# LCT_M3_SCH.net
KiCad netlist of a schematic drawn in Altium Designer
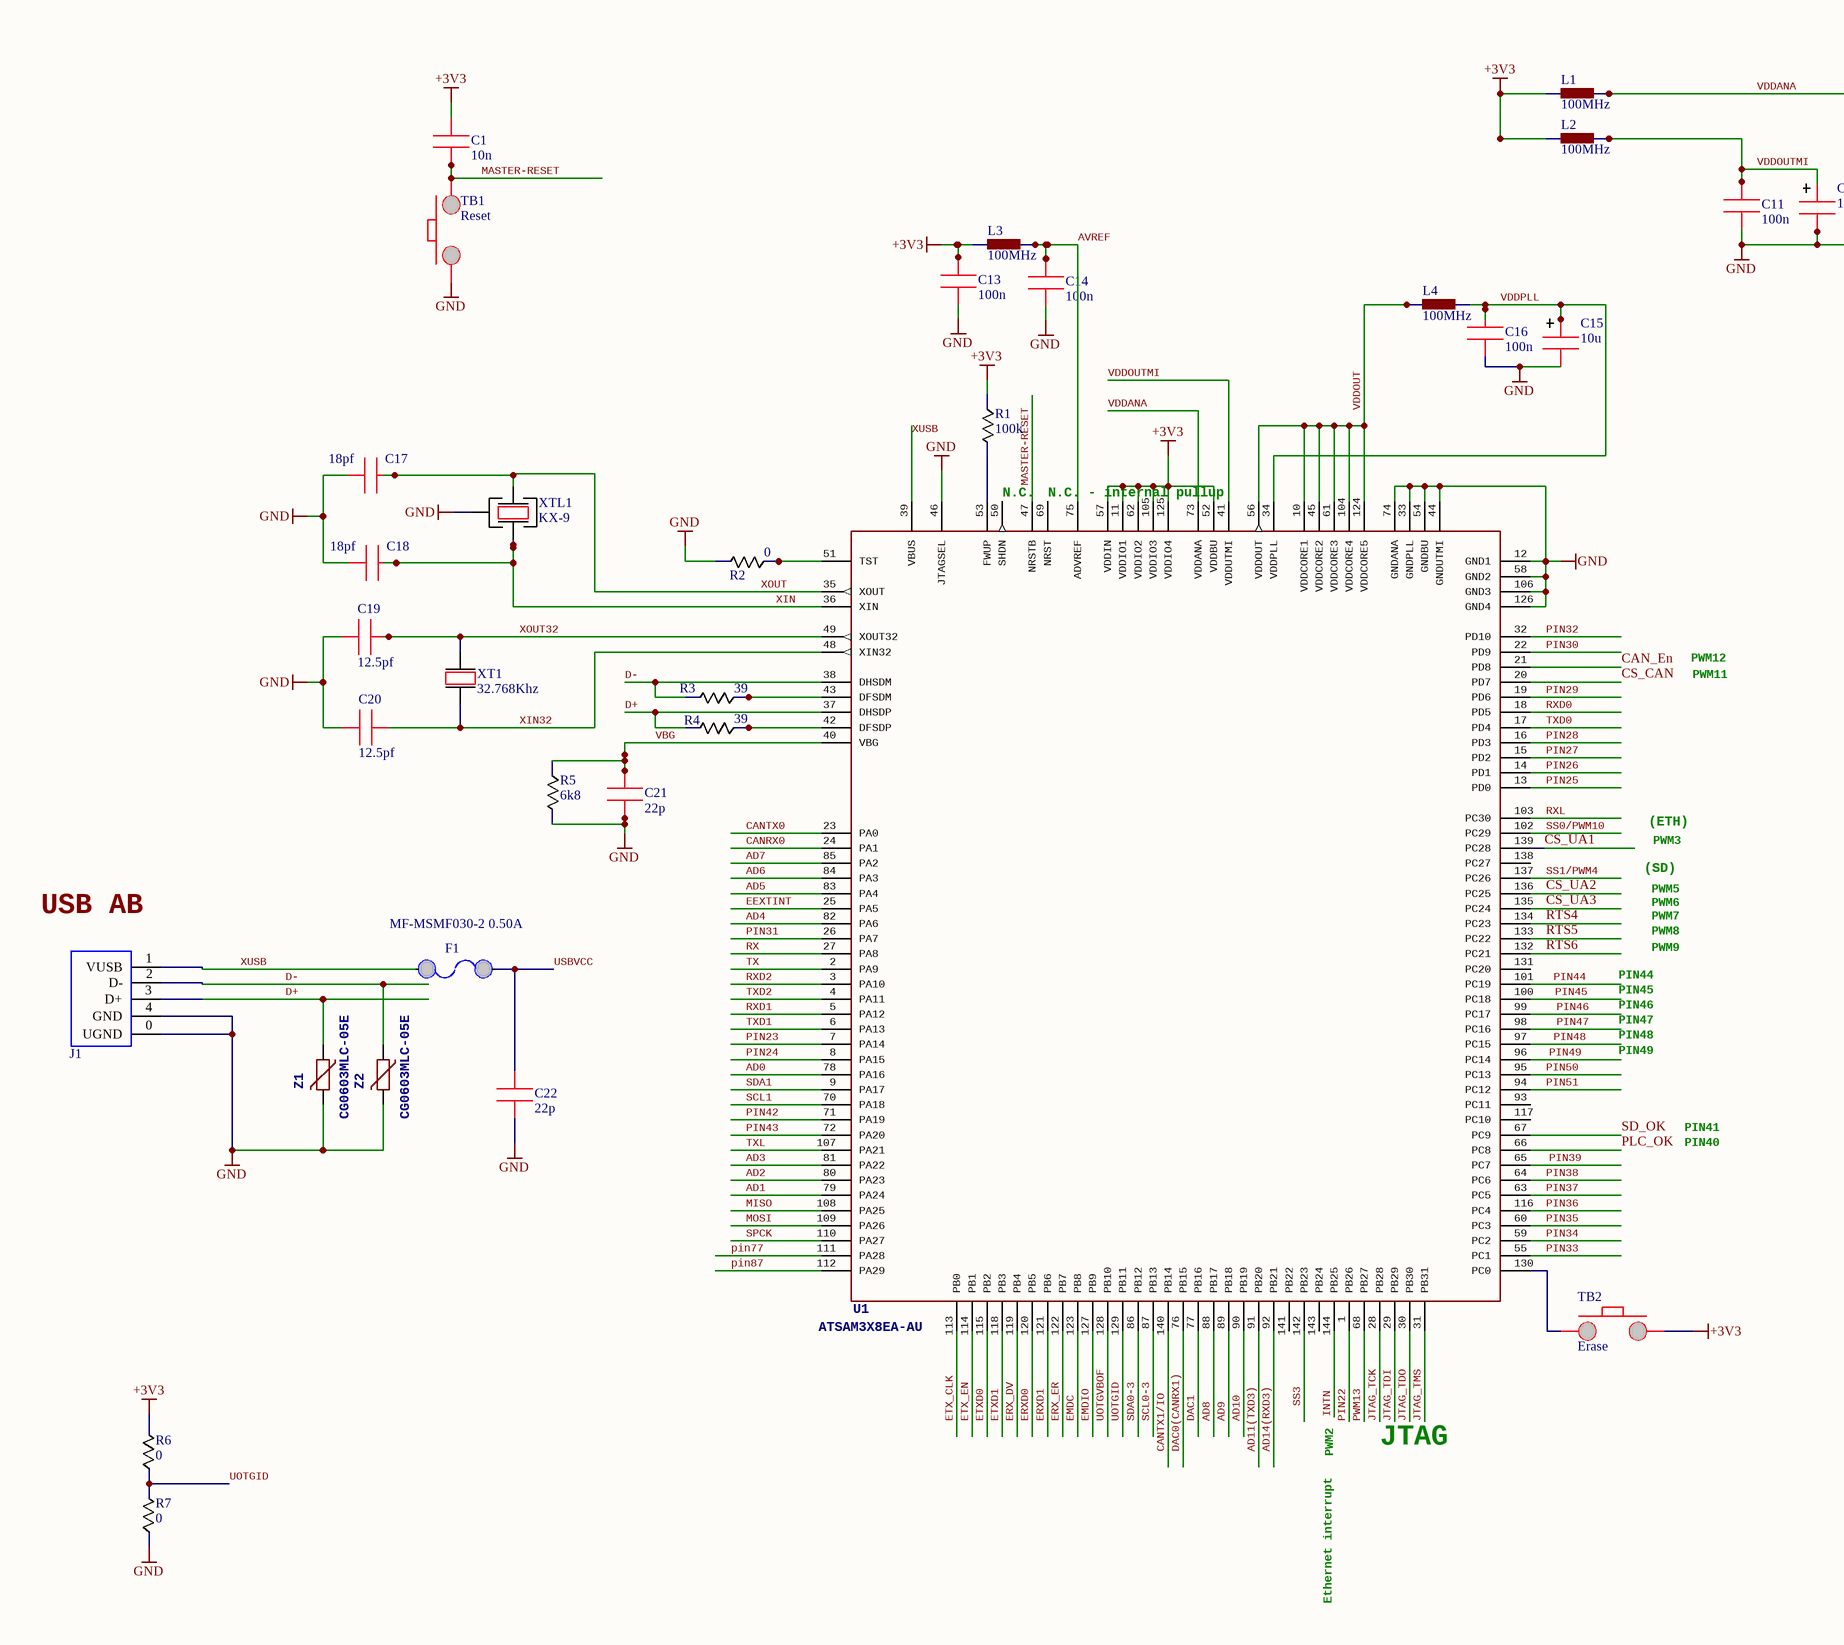
[diagram p0: LCT M3 SCH.SchDoc, left]
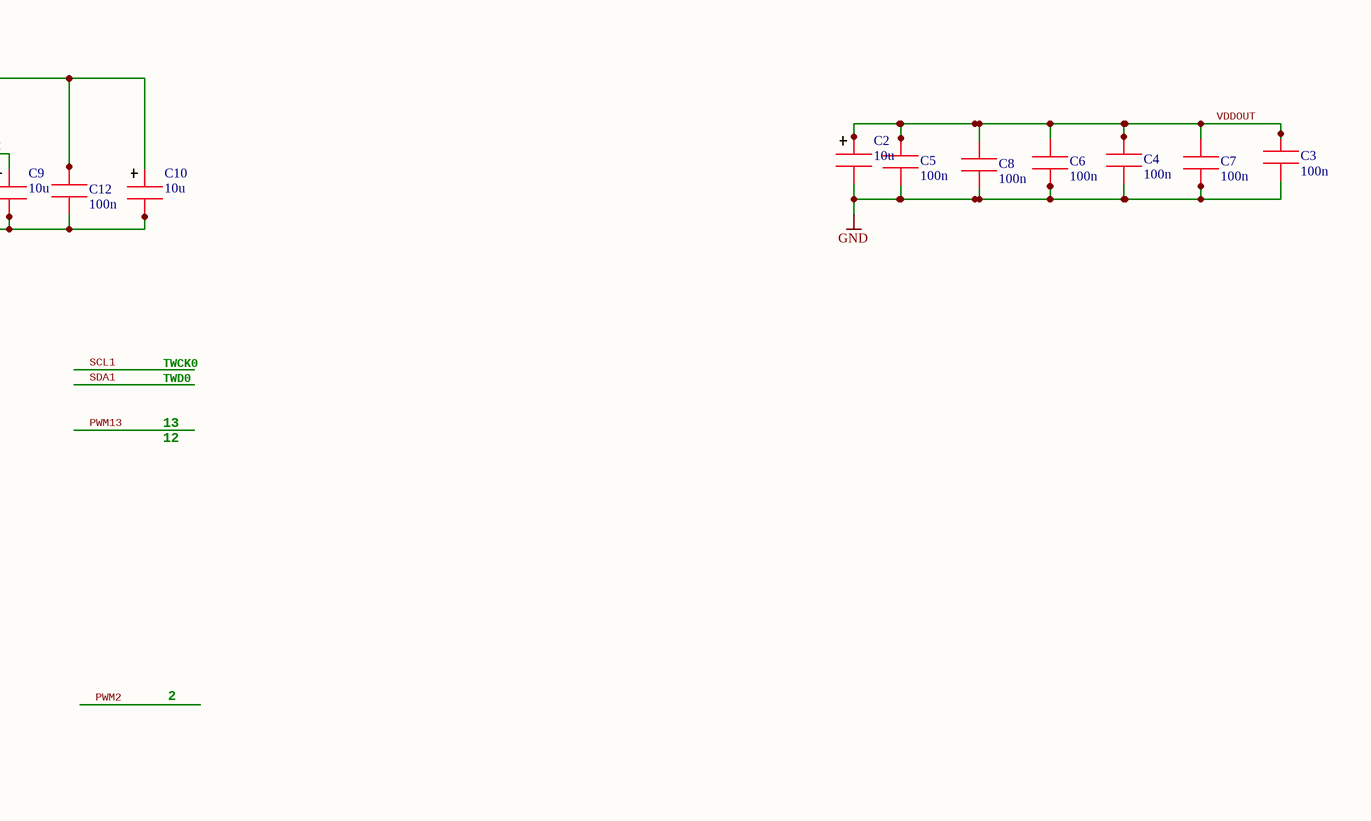
[diagram p1: LCT M3 SCH.SchDoc, right]

(export (version "E")
  (design (tool "Eeschema 10.0.6"))
  (components
    (comp (ref "C1") (value "10n") (footprint "0603") (libsource (lib "kontr") (part "Capasitor 0805")))
    (comp (ref "C2")
      (value "10u")
      (footprint "1206")
      (description "TAJA156K010RNJ")
      (libsource (lib "kontr") (part "1206 Cap El"))
    )
    (comp (ref "C3") (value "100n") (footprint "0603") (libsource (lib "kontr") (part "Capasitor 0805")))
    (comp (ref "C4") (value "100n") (footprint "0603") (libsource (lib "kontr") (part "Capasitor 0805")))
    (comp (ref "C5") (value "100n") (footprint "0603") (libsource (lib "kontr") (part "Capasitor 0805")))
    (comp (ref "C6") (value "100n") (footprint "0603") (libsource (lib "kontr") (part "Capasitor 0805")))
    (comp (ref "C7") (value "100n") (footprint "0603") (libsource (lib "kontr") (part "Capasitor 0805")))
    (comp (ref "C8") (value "100n") (footprint "0603") (libsource (lib "kontr") (part "Capasitor 0805")))
    (comp (ref "C9")
      (value "10u")
      (footprint "1206")
      (description "TAJA156K010RNJ")
      (libsource (lib "kontr") (part "1206 Cap El"))
    )
    (comp (ref "C10")
      (value "10u")
      (footprint "1206")
      (description "TAJA156K010RNJ")
      (libsource (lib "kontr") (part "1206 Cap El"))
    )
    (comp (ref "C11") (value "100n") (footprint "0603") (libsource (lib "kontr") (part "Capasitor 0805")))
    (comp (ref "C12") (value "100n") (footprint "0603") (libsource (lib "kontr") (part "Capasitor 0805")))
    (comp (ref "C13") (value "100n") (footprint "0603") (libsource (lib "kontr") (part "Capasitor 0805")))
    (comp (ref "C14") (value "100n") (footprint "0603") (libsource (lib "kontr") (part "Capasitor 0805")))
    (comp (ref "C15")
      (value "10u")
      (footprint "1206")
      (description "TAJA156K010RNJ")
      (libsource (lib "kontr") (part "1206 Cap El"))
    )
    (comp (ref "C16") (value "100n") (footprint "0603") (libsource (lib "kontr") (part "Capasitor 0805")))
    (comp (ref "C17") (value "18pf") (footprint "0603") (libsource (lib "kontr") (part "Capasitor 0805")))
    (comp (ref "C18") (value "18pf") (footprint "0603") (libsource (lib "kontr") (part "Capasitor 0805")))
    (comp (ref "C19") (value "12.5pf") (footprint "0603") (libsource (lib "kontr") (part "Capasitor 0805")))
    (comp (ref "C20") (value "12.5pf") (footprint "0603") (libsource (lib "kontr") (part "Capasitor 0805")))
    (comp (ref "C21") (value "22p") (footprint "0603") (libsource (lib "kontr") (part "Capasitor 0805")))
    (comp (ref "C22") (value "22p") (footprint "0603") (libsource (lib "kontr") (part "Capasitor 0805")))
    (comp (ref "F1")
      (value "MF-MSMF030-2 0.50A")
      (footprint "Fuse PTS")
      (libsource (lib "kontr") (part "Fuse PTS"))
    )
    (comp (ref "J1") (value "USBB-1J") (footprint "USB B") (libsource (lib "kontr") (part "USBB-1J")))
    (comp (ref "L1") (value "100MHz") (footprint "0805") (libsource (lib "kontr") (part "BLM21PG220SN1D")))
    (comp (ref "L2") (value "100MHz") (footprint "0805") (libsource (lib "kontr") (part "BLM21PG220SN1D")))
    (comp (ref "L3") (value "100MHz") (footprint "0805") (libsource (lib "kontr") (part "BLM21PG220SN1D")))
    (comp (ref "L4") (value "100MHz") (footprint "0805") (libsource (lib "kontr") (part "BLM21PG220SN1D")))
    (comp (ref "R1")
      (value "100k")
      (footprint "0603")
      (description "0805 SMD Resistor")
      (libsource (lib "kontr") (part "Resistor 0805"))
    )
    (comp (ref "R2")
      (value "0")
      (footprint "0603")
      (description "0805 SMD Resistor")
      (libsource (lib "kontr") (part "Resistor 0805"))
    )
    (comp (ref "R3")
      (value "39")
      (footprint "0603")
      (description "0805 SMD Resistor")
      (libsource (lib "kontr") (part "Resistor 0805"))
    )
    (comp (ref "R4")
      (value "39")
      (footprint "0603")
      (description "0805 SMD Resistor")
      (libsource (lib "kontr") (part "Resistor 0805"))
    )
    (comp (ref "R5")
      (value "6k8")
      (footprint "0603")
      (description "0805 SMD Resistor")
      (libsource (lib "kontr") (part "Resistor 0805"))
    )
    (comp (ref "R6")
      (value "0")
      (footprint "0603")
      (description "RC0603FR-078K2")
      (libsource (lib "kontr") (part "Resistor 0805"))
    )
    (comp (ref "R7")
      (value "0")
      (footprint "0603")
      (description "RC0603FR-078K2")
      (libsource (lib "kontr") (part "Resistor 0805"))
    )
    (comp (ref "TB1")
      (value "Reset")
      (footprint "IT-1184-160G-g")
      (description "IT-1184-160G-G")
      (libsource (lib "kontr") (part "IT-1184-160G-G"))
    )
    (comp (ref "TB2")
      (value "Erase")
      (footprint "IT-1184-160G-g")
      (description "IT-1184-160G-G")
      (libsource (lib "kontr") (part "IT-1184-160G-G"))
    )
    (comp (ref "U1")
      (value "ATSAM3X8EA-AU")
      (footprint "LQFP144")
      (libsource (lib "SmartPrj") (part "ATSAM3X/AAU"))
    )
    (comp (ref "XT1")
      (value "32.768Khz")
      (footprint "KX – 327")
      (description "KX – 327XS")
      (libsource (lib "kontr") (part "KX – 327XS"))
    )
    (comp (ref "XTL1") (value "KX-9") (footprint "KX-9") (libsource (lib "kontr") (part "KX-9")))
    (comp (ref "Z1")
      (value "CG0603MLC-05E")
      (footprint "0603")
      (description "<b>VARISTOR</b>")
      (libsource (lib "varistor") (part "VARISTORCN0603"))
    )
    (comp (ref "Z2")
      (value "CG0603MLC-05E")
      (footprint "0603")
      (description "<b>VARISTOR</b>")
      (libsource (lib "varistor") (part "VARISTORCN0603"))
    )
  )
  (nets
    (net (code "1") (name "+3V3") (class "Default")
      (node (ref "C1") (pin "2") (pinfunction "2_2") (pintype "passive"))
      (node (ref "C13") (pin "2") (pinfunction "2_2") (pintype "passive"))
      (node (ref "L1") (pin "1") (pintype "passive"))
      (node (ref "L2") (pin "1") (pintype "passive"))
      (node (ref "L3") (pin "1") (pintype "passive"))
      (node (ref "R1") (pin "1") (pintype "passive"))
      (node (ref "R6") (pin "2") (pintype "passive"))
      (node (ref "TB2") (pin "1") (pinfunction "1_1") (pintype "passive"))
      (node (ref "U1") (pin "105") (pinfunction "VDDIO3_105") (pintype "power_in"))
      (node (ref "U1") (pin "11") (pinfunction "VDDIO1_11") (pintype "power_in"))
      (node (ref "U1") (pin "125") (pinfunction "VDDIO4_125") (pintype "power_in"))
      (node (ref "U1") (pin "52") (pinfunction "VDDBU_52") (pintype "power_in"))
      (node (ref "U1") (pin "57") (pinfunction "VDDIN_57") (pintype "power_in"))
      (node (ref "U1") (pin "62") (pinfunction "VDDIO2_62") (pintype "power_in"))
    )
    (net (code "2") (name "/AD0") (class "Default")
      (node (ref "U1") (pin "78") (pinfunction "PA16_78") (pintype "passive"))
    )
    (net (code "3") (name "/AD1") (class "Default")
      (node (ref "U1") (pin "79") (pinfunction "PA24_79") (pintype "passive"))
    )
    (net (code "4") (name "/AD2") (class "Default")
      (node (ref "U1") (pin "80") (pinfunction "PA23_80") (pintype "passive"))
    )
    (net (code "5") (name "/AD3") (class "Default")
      (node (ref "U1") (pin "81") (pinfunction "PA22_81") (pintype "passive"))
    )
    (net (code "6") (name "/AD4") (class "Default")
      (node (ref "U1") (pin "82") (pinfunction "PA6_82") (pintype "passive"))
    )
    (net (code "7") (name "/AD5") (class "Default")
      (node (ref "U1") (pin "83") (pinfunction "PA4_83") (pintype "passive"))
    )
    (net (code "8") (name "/AD6") (class "Default")
      (node (ref "U1") (pin "84") (pinfunction "PA3_84") (pintype "passive"))
    )
    (net (code "9") (name "/AD7") (class "Default")
      (node (ref "U1") (pin "85") (pinfunction "PA2_85") (pintype "passive"))
    )
    (net (code "10") (name "/AD8") (class "Default")
      (node (ref "U1") (pin "88") (pinfunction "PB17_88") (pintype "passive"))
    )
    (net (code "11") (name "/AD9") (class "Default")
      (node (ref "U1") (pin "89") (pinfunction "PB18_89") (pintype "passive"))
    )
    (net (code "12") (name "/AD10") (class "Default")
      (node (ref "U1") (pin "90") (pinfunction "PB19_90") (pintype "passive"))
    )
    (net (code "13") (name "/AD11(TXD3)") (class "Default")
      (node (ref "U1") (pin "91") (pinfunction "PB20_91") (pintype "passive"))
    )
    (net (code "14") (name "/AD14(RXD3)") (class "Default")
      (node (ref "U1") (pin "92") (pinfunction "PB21_92") (pintype "passive"))
    )
    (net (code "15") (name "/AVREF") (class "Default")
      (node (ref "C14") (pin "2") (pinfunction "2_2") (pintype "passive"))
      (node (ref "L3") (pin "2") (pintype "passive"))
      (node (ref "U1") (pin "75") (pinfunction "ADVREF_75") (pintype "power_in"))
    )
    (net (code "16") (name "/CANRX0") (class "Default")
      (node (ref "U1") (pin "24") (pinfunction "PA1_24") (pintype "passive"))
    )
    (net (code "17") (name "/CANTX0") (class "Default")
      (node (ref "U1") (pin "23") (pinfunction "PA0_23") (pintype "passive"))
    )
    (net (code "18") (name "/CANTX1{slash}IO") (class "Default")
      (node (ref "U1") (pin "140") (pinfunction "PB14_140") (pintype "passive"))
    )
    (net (code "19") (name "/CAN_En") (class "Default")
      (node (ref "U1") (pin "21") (pinfunction "PD8_21") (pintype "passive"))
    )
    (net (code "20") (name "/CS_CAN") (class "Default")
      (node (ref "U1") (pin "20") (pinfunction "PD7_20") (pintype "passive"))
    )
    (net (code "21") (name "/CS_UA1") (class "Default")
      (node (ref "U1") (pin "139") (pinfunction "PC28_139") (pintype "passive"))
    )
    (net (code "22") (name "/CS_UA2") (class "Default")
      (node (ref "U1") (pin "136") (pinfunction "PC25_136") (pintype "passive"))
    )
    (net (code "23") (name "/CS_UA3") (class "Default")
      (node (ref "U1") (pin "135") (pinfunction "PC24_135") (pintype "passive"))
    )
    (net (code "24") (name "/D+") (class "Default")
      (node (ref "J1") (pin "3") (pinfunction "D+_3") (pintype "passive"))
      (node (ref "R4") (pin "2") (pintype "passive"))
      (node (ref "U1") (pin "37") (pinfunction "DHSDP_37") (pintype "passive"))
      (node (ref "Z1") (pin "1") (pinfunction "1_1") (pintype "passive"))
    )
    (net (code "25") (name "/D-") (class "Default")
      (node (ref "J1") (pin "2") (pinfunction "D-_2") (pintype "passive"))
      (node (ref "R3") (pin "2") (pintype "passive"))
      (node (ref "U1") (pin "38") (pinfunction "DHSDM_38") (pintype "passive"))
      (node (ref "Z2") (pin "1") (pinfunction "1_1") (pintype "passive"))
    )
    (net (code "26") (name "/DAC0(CANRX1)") (class "Default")
      (node (ref "U1") (pin "76") (pinfunction "PB15_76") (pintype "passive"))
    )
    (net (code "27") (name "/DAC1") (class "Default")
      (node (ref "U1") (pin "77") (pinfunction "PB16_77") (pintype "passive"))
    )
    (net (code "28") (name "/EEXTINT") (class "Default")
      (node (ref "U1") (pin "25") (pinfunction "PA5_25") (pintype "passive"))
    )
    (net (code "29") (name "/EMDC") (class "Default")
      (node (ref "U1") (pin "123") (pinfunction "PB8_123") (pintype "passive"))
    )
    (net (code "30") (name "/EMDIO") (class "Default")
      (node (ref "U1") (pin "127") (pinfunction "PB9_127") (pintype "passive"))
    )
    (net (code "31") (name "/ERXD0") (class "Default")
      (node (ref "U1") (pin "120") (pinfunction "PB5_120") (pintype "passive"))
    )
    (net (code "32") (name "/ERXD1") (class "Default")
      (node (ref "U1") (pin "121") (pinfunction "PB6_121") (pintype "passive"))
    )
    (net (code "33") (name "/ERX_DV") (class "Default")
      (node (ref "U1") (pin "119") (pinfunction "PB4_119") (pintype "passive"))
    )
    (net (code "34") (name "/ERX_ER") (class "Default")
      (node (ref "U1") (pin "122") (pinfunction "PB7_122") (pintype "passive"))
    )
    (net (code "35") (name "/ETXD0") (class "Default")
      (node (ref "U1") (pin "115") (pinfunction "PB2_115") (pintype "passive"))
    )
    (net (code "36") (name "/ETXD1") (class "Default")
      (node (ref "U1") (pin "118") (pinfunction "PB3_118") (pintype "passive"))
    )
    (net (code "37") (name "/ETX_CLK") (class "Default")
      (node (ref "U1") (pin "113") (pinfunction "PB0_113") (pintype "passive"))
    )
    (net (code "38") (name "/ETX_EN") (class "Default")
      (node (ref "U1") (pin "114") (pinfunction "PB1_114") (pintype "passive"))
    )
    (net (code "39") (name "/INTN") (class "Default")
      (node (ref "U1") (pin "144") (pinfunction "PB25_144") (pintype "passive"))
    )
    (net (code "40") (name "/JTAG_TCK") (class "Default")
      (node (ref "U1") (pin "28") (pinfunction "PB28_28") (pintype "passive"))
    )
    (net (code "41") (name "/JTAG_TDI") (class "Default")
      (node (ref "U1") (pin "29") (pinfunction "PB29_29") (pintype "passive"))
    )
    (net (code "42") (name "/JTAG_TDO") (class "Default")
      (node (ref "U1") (pin "30") (pinfunction "PB30_30") (pintype "passive"))
    )
    (net (code "43") (name "/JTAG_TMS") (class "Default")
      (node (ref "U1") (pin "31") (pinfunction "PB31_31") (pintype "passive"))
    )
    (net (code "44") (name "/MASTER-RESET") (class "Default")
      (node (ref "C1") (pin "1") (pinfunction "1_1") (pintype "passive"))
      (node (ref "TB1") (pin "1") (pinfunction "1_1") (pintype "passive"))
      (node (ref "U1") (pin "47") (pinfunction "NRSTB_47") (pintype "passive"))
    )
    (net (code "45") (name "/MISO") (class "Default")
      (node (ref "U1") (pin "108") (pinfunction "PA25_108") (pintype "passive"))
    )
    (net (code "46") (name "/MOSI") (class "Default")
      (node (ref "U1") (pin "109") (pinfunction "PA26_109") (pintype "passive"))
    )
    (net (code "47") (name "/PIN22") (class "Default")
      (node (ref "U1") (pin "1") (pinfunction "PB26_1") (pintype "passive"))
    )
    (net (code "48") (name "/PIN23") (class "Default")
      (node (ref "U1") (pin "7") (pinfunction "PA14_7") (pintype "passive"))
    )
    (net (code "49") (name "/PIN24") (class "Default")
      (node (ref "U1") (pin "8") (pinfunction "PA15_8") (pintype "passive"))
    )
    (net (code "50") (name "/PIN25") (class "Default")
      (node (ref "U1") (pin "13") (pinfunction "PD0_13") (pintype "passive"))
    )
    (net (code "51") (name "/PIN26") (class "Default")
      (node (ref "U1") (pin "14") (pinfunction "PD1_14") (pintype "passive"))
    )
    (net (code "52") (name "/PIN27") (class "Default")
      (node (ref "U1") (pin "15") (pinfunction "PD2_15") (pintype "passive"))
    )
    (net (code "53") (name "/PIN28") (class "Default")
      (node (ref "U1") (pin "16") (pinfunction "PD3_16") (pintype "passive"))
    )
    (net (code "54") (name "/PIN29") (class "Default")
      (node (ref "U1") (pin "19") (pinfunction "PD6_19") (pintype "passive"))
    )
    (net (code "55") (name "/PIN30") (class "Default")
      (node (ref "U1") (pin "22") (pinfunction "PD9_22") (pintype "passive"))
    )
    (net (code "56") (name "/PIN31") (class "Default")
      (node (ref "U1") (pin "26") (pinfunction "PA7_26") (pintype "passive"))
    )
    (net (code "57") (name "/PIN32") (class "Default")
      (node (ref "U1") (pin "32") (pinfunction "PD10_32") (pintype "passive"))
    )
    (net (code "58") (name "/PIN33") (class "Default")
      (node (ref "U1") (pin "55") (pinfunction "PC1_55") (pintype "passive"))
    )
    (net (code "59") (name "/PIN34") (class "Default")
      (node (ref "U1") (pin "59") (pinfunction "PC2_59") (pintype "passive"))
    )
    (net (code "60") (name "/PIN35") (class "Default")
      (node (ref "U1") (pin "60") (pinfunction "PC3_60") (pintype "passive"))
    )
    (net (code "61") (name "/PIN36") (class "Default")
      (node (ref "U1") (pin "116") (pinfunction "PC4_116") (pintype "passive"))
    )
    (net (code "62") (name "/PIN37") (class "Default")
      (node (ref "U1") (pin "63") (pinfunction "PC5_63") (pintype "passive"))
    )
    (net (code "63") (name "/PIN38") (class "Default")
      (node (ref "U1") (pin "64") (pinfunction "PC6_64") (pintype "passive"))
    )
    (net (code "64") (name "/PIN39") (class "Default")
      (node (ref "U1") (pin "65") (pinfunction "PC7_65") (pintype "passive"))
    )
    (net (code "65") (name "/PIN42") (class "Default")
      (node (ref "U1") (pin "71") (pinfunction "PA19_71") (pintype "passive"))
    )
    (net (code "66") (name "/PIN43") (class "Default")
      (node (ref "U1") (pin "72") (pinfunction "PA20_72") (pintype "passive"))
    )
    (net (code "67") (name "/PIN44") (class "Default")
      (node (ref "U1") (pin "101") (pinfunction "PC19_101") (pintype "passive"))
    )
    (net (code "68") (name "/PIN45") (class "Default")
      (node (ref "U1") (pin "100") (pinfunction "PC18_100") (pintype "passive"))
    )
    (net (code "69") (name "/PIN46") (class "Default")
      (node (ref "U1") (pin "99") (pinfunction "PC17_99") (pintype "passive"))
    )
    (net (code "70") (name "/PIN47") (class "Default")
      (node (ref "U1") (pin "98") (pinfunction "PC16_98") (pintype "passive"))
    )
    (net (code "71") (name "/PIN48") (class "Default")
      (node (ref "U1") (pin "97") (pinfunction "PC15_97") (pintype "passive"))
    )
    (net (code "72") (name "/PIN49") (class "Default")
      (node (ref "U1") (pin "96") (pinfunction "PC14_96") (pintype "passive"))
    )
    (net (code "73") (name "/PIN50") (class "Default")
      (node (ref "U1") (pin "95") (pinfunction "PC13_95") (pintype "passive"))
    )
    (net (code "74") (name "/PIN51") (class "Default")
      (node (ref "U1") (pin "94") (pinfunction "PC12_94") (pintype "passive"))
    )
    (net (code "75") (name "/PLC_OK") (class "Default")
      (node (ref "U1") (pin "66") (pinfunction "PC8_66") (pintype "passive"))
    )
    (net (code "77") (name "/PWM13") (class "Default")
      (node (ref "U1") (pin "68") (pinfunction "PB27_68") (pintype "passive"))
    )
    (net (code "78") (name "/RTS4") (class "Default")
      (node (ref "U1") (pin "134") (pinfunction "PC23_134") (pintype "passive"))
    )
    (net (code "79") (name "/RTS5") (class "Default")
      (node (ref "U1") (pin "133") (pinfunction "PC22_133") (pintype "passive"))
    )
    (net (code "80") (name "/RTS6") (class "Default")
      (node (ref "U1") (pin "132") (pinfunction "PC21_132") (pintype "passive"))
    )
    (net (code "81") (name "/RX") (class "Default")
      (node (ref "U1") (pin "27") (pinfunction "PA8_27") (pintype "passive"))
    )
    (net (code "82") (name "/RXD0") (class "Default")
      (node (ref "U1") (pin "18") (pinfunction "PD5_18") (pintype "passive"))
    )
    (net (code "83") (name "/RXD1") (class "Default")
      (node (ref "U1") (pin "5") (pinfunction "PA12_5") (pintype "passive"))
    )
    (net (code "84") (name "/RXD2") (class "Default")
      (node (ref "U1") (pin "3") (pinfunction "PA10_3") (pintype "passive"))
    )
    (net (code "85") (name "/RXL") (class "Default")
      (node (ref "U1") (pin "103") (pinfunction "PC30_103") (pintype "passive"))
    )
    (net (code "86") (name "/SCL0-3") (class "Default")
      (node (ref "U1") (pin "87") (pinfunction "PB13_87") (pintype "passive"))
    )
    (net (code "87") (name "/SCL1") (class "Default")
      (node (ref "U1") (pin "70") (pinfunction "PA18_70") (pintype "passive"))
    )
    (net (code "88") (name "/SDA0-3") (class "Default")
      (node (ref "U1") (pin "86") (pinfunction "PB12_86") (pintype "passive"))
    )
    (net (code "89") (name "/SDA1") (class "Default")
      (node (ref "U1") (pin "9") (pinfunction "PA17_9") (pintype "passive"))
    )
    (net (code "90") (name "/SD_OK") (class "Default")
      (node (ref "U1") (pin "67") (pinfunction "PC9_67") (pintype "passive"))
    )
    (net (code "91") (name "/SPCK") (class "Default")
      (node (ref "U1") (pin "110") (pinfunction "PA27_110") (pintype "passive"))
    )
    (net (code "92") (name "/SS0{slash}PWM10") (class "Default")
      (node (ref "U1") (pin "102") (pinfunction "PC29_102") (pintype "passive"))
    )
    (net (code "93") (name "/SS1{slash}PWM4") (class "Default")
      (node (ref "U1") (pin "137") (pinfunction "PC26_137") (pintype "passive"))
    )
    (net (code "94") (name "/SS3") (class "Default")
      (node (ref "U1") (pin "142") (pinfunction "PB23_142") (pintype "passive"))
    )
    (net (code "95") (name "/TX") (class "Default")
      (node (ref "U1") (pin "2") (pinfunction "PA9_2") (pintype "passive"))
    )
    (net (code "96") (name "/TXD0") (class "Default")
      (node (ref "U1") (pin "17") (pinfunction "PD4_17") (pintype "passive"))
    )
    (net (code "97") (name "/TXD1") (class "Default")
      (node (ref "U1") (pin "6") (pinfunction "PA13_6") (pintype "passive"))
    )
    (net (code "98") (name "/TXD2") (class "Default")
      (node (ref "U1") (pin "4") (pinfunction "PA11_4") (pintype "passive"))
    )
    (net (code "99") (name "/TXL") (class "Default")
      (node (ref "U1") (pin "107") (pinfunction "PA21_107") (pintype "passive"))
    )
    (net (code "100") (name "/UOTGID") (class "Default")
      (node (ref "R6") (pin "1") (pintype "passive"))
      (node (ref "R7") (pin "2") (pintype "passive"))
      (node (ref "U1") (pin "129") (pinfunction "PB11_129") (pintype "passive"))
    )
    (net (code "101") (name "/UOTGVBOF") (class "Default")
      (node (ref "U1") (pin "128") (pinfunction "PB10_128") (pintype "passive"))
    )
    (net (code "102") (name "/USBVCC") (class "Default")
      (node (ref "C22") (pin "1") (pinfunction "1_1") (pintype "passive"))
      (node (ref "F1") (pin "1") (pinfunction "1_1") (pintype "passive"))
    )
    (net (code "103") (name "/VBG") (class "Default")
      (node (ref "C21") (pin "2") (pinfunction "2_2") (pintype "passive"))
      (node (ref "R5") (pin "1") (pintype "passive"))
      (node (ref "U1") (pin "40") (pinfunction "VBG_40") (pintype "passive"))
    )
    (net (code "104") (name "/VDDANA") (class "Default")
      (node (ref "C10") (pin "1") (pinfunction "1_1") (pintype "passive"))
      (node (ref "C12") (pin "2") (pinfunction "2_2") (pintype "passive"))
      (node (ref "L1") (pin "2") (pintype "passive"))
      (node (ref "U1") (pin "73") (pinfunction "VDDANA_73") (pintype "power_in"))
    )
    (net (code "105") (name "/VDDOUT") (class "Default")
      (node (ref "C2") (pin "1") (pinfunction "1_1") (pintype "passive"))
      (node (ref "C3") (pin "2") (pinfunction "2_2") (pintype "passive"))
      (node (ref "C4") (pin "2") (pinfunction "2_2") (pintype "passive"))
      (node (ref "C5") (pin "2") (pinfunction "2_2") (pintype "passive"))
      (node (ref "C6") (pin "2") (pinfunction "2_2") (pintype "passive"))
      (node (ref "C7") (pin "2") (pinfunction "2_2") (pintype "passive"))
      (node (ref "C8") (pin "2") (pinfunction "2_2") (pintype "passive"))
      (node (ref "L4") (pin "1") (pintype "passive"))
      (node (ref "U1") (pin "10") (pinfunction "VDDCORE1_10") (pintype "passive"))
      (node (ref "U1") (pin "104") (pinfunction "VDDCORE4_104") (pintype "passive"))
      (node (ref "U1") (pin "124") (pinfunction "VDDCORE5_124") (pintype "passive"))
      (node (ref "U1") (pin "45") (pinfunction "VDDCORE2_45") (pintype "passive"))
      (node (ref "U1") (pin "56") (pinfunction "VDDOUT_56") (pintype "output"))
      (node (ref "U1") (pin "61") (pinfunction "VDDCORE3_61") (pintype "passive"))
    )
    (net (code "106") (name "/VDDOUTMI") (class "Default")
      (node (ref "C11") (pin "2") (pinfunction "2_2") (pintype "passive"))
      (node (ref "C9") (pin "1") (pinfunction "1_1") (pintype "passive"))
      (node (ref "L2") (pin "2") (pintype "passive"))
      (node (ref "U1") (pin "41") (pinfunction "VDDUTMI_41") (pintype "passive"))
    )
    (net (code "107") (name "/VDDPLL") (class "Default")
      (node (ref "C15") (pin "1") (pinfunction "1_1") (pintype "passive"))
      (node (ref "C16") (pin "2") (pinfunction "2_2") (pintype "passive"))
      (node (ref "L4") (pin "2") (pintype "passive"))
      (node (ref "U1") (pin "34") (pinfunction "VDDPLL_34") (pintype "passive"))
    )
    (net (code "108") (name "/XIN") (class "Default")
      (node (ref "C18") (pin "2") (pinfunction "2_2") (pintype "passive"))
      (node (ref "U1") (pin "36") (pinfunction "XIN_36") (pintype "passive"))
      (node (ref "XTL1") (pin "3") (pinfunction "5_3") (pintype "passive"))
    )
    (net (code "109") (name "/XIN32") (class "Default")
      (node (ref "C20") (pin "1") (pinfunction "1_1") (pintype "passive"))
      (node (ref "U1") (pin "48") (pinfunction "XIN32_48") (pintype "output"))
      (node (ref "XT1") (pin "1") (pinfunction "5_1") (pintype "passive"))
    )
    (net (code "110") (name "/XOUT") (class "Default")
      (node (ref "C17") (pin "2") (pinfunction "2_2") (pintype "passive"))
      (node (ref "U1") (pin "35") (pinfunction "XOUT_35") (pintype "output"))
      (node (ref "XTL1") (pin "1") (pinfunction "5_1") (pintype "passive"))
    )
    (net (code "111") (name "/XOUT32") (class "Default")
      (node (ref "C19") (pin "1") (pinfunction "1_1") (pintype "passive"))
      (node (ref "U1") (pin "49") (pinfunction "XOUT32_49") (pintype "output"))
      (node (ref "XT1") (pin "2") (pinfunction "5_2") (pintype "passive"))
    )
    (net (code "112") (name "/XUSB") (class "Default")
      (node (ref "F1") (pin "2") (pinfunction "2_2") (pintype "passive"))
      (node (ref "J1") (pin "1") (pinfunction "VUSB_1") (pintype "passive"))
      (node (ref "U1") (pin "39") (pinfunction "VBUS_39") (pintype "power_in"))
    )
    (net (code "113") (name "/pin77") (class "Default")
      (node (ref "U1") (pin "111") (pinfunction "PA28_111") (pintype "passive"))
    )
    (net (code "114") (name "/pin87") (class "Default")
      (node (ref "U1") (pin "112") (pinfunction "PA29_112") (pintype "passive"))
    )
    (net (code "115") (name "GND") (class "Default")
      (node (ref "C10") (pin "2") (pinfunction "2_2") (pintype "passive"))
      (node (ref "C11") (pin "1") (pinfunction "1_1") (pintype "passive"))
      (node (ref "C12") (pin "1") (pinfunction "1_1") (pintype "passive"))
      (node (ref "C13") (pin "1") (pinfunction "1_1") (pintype "passive"))
      (node (ref "C14") (pin "1") (pinfunction "1_1") (pintype "passive"))
      (node (ref "C15") (pin "2") (pinfunction "2_2") (pintype "passive"))
      (node (ref "C16") (pin "1") (pinfunction "1_1") (pintype "passive"))
      (node (ref "C17") (pin "1") (pinfunction "1_1") (pintype "passive"))
      (node (ref "C18") (pin "1") (pinfunction "1_1") (pintype "passive"))
      (node (ref "C19") (pin "2") (pinfunction "2_2") (pintype "passive"))
      (node (ref "C2") (pin "2") (pinfunction "2_2") (pintype "passive"))
      (node (ref "C20") (pin "2") (pinfunction "2_2") (pintype "passive"))
      (node (ref "C21") (pin "1") (pinfunction "1_1") (pintype "passive"))
      (node (ref "C22") (pin "2") (pinfunction "2_2") (pintype "passive"))
      (node (ref "C3") (pin "1") (pinfunction "1_1") (pintype "passive"))
      (node (ref "C4") (pin "1") (pinfunction "1_1") (pintype "passive"))
      (node (ref "C5") (pin "1") (pinfunction "1_1") (pintype "passive"))
      (node (ref "C6") (pin "1") (pinfunction "1_1") (pintype "passive"))
      (node (ref "C7") (pin "1") (pinfunction "1_1") (pintype "passive"))
      (node (ref "C8") (pin "1") (pinfunction "1_1") (pintype "passive"))
      (node (ref "C9") (pin "2") (pinfunction "2_2") (pintype "passive"))
      (node (ref "J1") (pin "0") (pinfunction "UGND_0") (pintype "passive"))
      (node (ref "J1") (pin "4") (pinfunction "GND_4") (pintype "passive"))
      (node (ref "R2") (pin "2") (pintype "passive"))
      (node (ref "R5") (pin "2") (pintype "passive"))
      (node (ref "R7") (pin "1") (pintype "passive"))
      (node (ref "TB1") (pin "2") (pinfunction "2_2") (pintype "passive"))
      (node (ref "U1") (pin "106") (pinfunction "GND3_106") (pintype "power_in"))
      (node (ref "U1") (pin "12") (pinfunction "GND1_12") (pintype "power_in"))
      (node (ref "U1") (pin "126") (pinfunction "GND4_126") (pintype "power_in"))
      (node (ref "U1") (pin "33") (pinfunction "GNDPLL_33") (pintype "power_in"))
      (node (ref "U1") (pin "44") (pinfunction "GNDUTMI_44") (pintype "power_in"))
      (node (ref "U1") (pin "46") (pinfunction "JTAGSEL_46") (pintype "passive"))
      (node (ref "U1") (pin "54") (pinfunction "GNDBU_54") (pintype "power_in"))
      (node (ref "U1") (pin "58") (pinfunction "GND2_58") (pintype "power_in"))
      (node (ref "U1") (pin "74") (pinfunction "GNDANA_74") (pintype "power_in"))
      (node (ref "XTL1") (pin "g") (pinfunction "5_g") (pintype "passive"))
      (node (ref "Z1") (pin "2") (pinfunction "2_2") (pintype "passive"))
      (node (ref "Z2") (pin "2") (pinfunction "2_2") (pintype "passive"))
    )
    (net (code "116") (name "Net-(U1-DFSDM)") (class "Default")
      (node (ref "R3") (pin "1") (pintype "passive"))
      (node (ref "U1") (pin "43") (pinfunction "DFSDM_43") (pintype "passive"))
    )
    (net (code "117") (name "Net-(U1-DFSDP)") (class "Default")
      (node (ref "R4") (pin "1") (pintype "passive"))
      (node (ref "U1") (pin "42") (pinfunction "DFSDP_42") (pintype "passive"))
    )
    (net (code "118") (name "Net-(U1-FWUP)") (class "Default")
      (node (ref "R1") (pin "2") (pintype "passive"))
      (node (ref "U1") (pin "53") (pinfunction "FWUP_53") (pintype "passive"))
    )
    (net (code "119") (name "Net-(U1-PC0)") (class "Default")
      (node (ref "TB2") (pin "2") (pinfunction "2_2") (pintype "passive"))
      (node (ref "U1") (pin "130") (pinfunction "PC0_130") (pintype "passive"))
    )
    (net (code "120") (name "Net-(U1-TST)") (class "Default")
      (node (ref "R2") (pin "1") (pintype "passive"))
      (node (ref "U1") (pin "51") (pinfunction "TST_51") (pintype "passive"))
    )
    (net (code "121") (name "unconnected-(U1-NRST-Pad69)") (class "Default")
      (node (ref "U1") (pin "69") (pinfunction "NRST_69") (pintype "passive"))
    )
    (net (code "122") (name "unconnected-(U1-PB22-Pad141)") (class "Default")
      (node (ref "U1") (pin "141") (pinfunction "PB22_141") (pintype "passive"))
    )
    (net (code "123") (name "unconnected-(U1-PB24-Pad143)") (class "Default")
      (node (ref "U1") (pin "143") (pinfunction "PB24_143") (pintype "passive"))
    )
    (net (code "124") (name "unconnected-(U1-PC10-Pad117)") (class "Default")
      (node (ref "U1") (pin "117") (pinfunction "PC10_117") (pintype "passive"))
    )
    (net (code "125") (name "unconnected-(U1-PC11-Pad93)") (class "Default")
      (node (ref "U1") (pin "93") (pinfunction "PC11_93") (pintype "passive"))
    )
    (net (code "126") (name "unconnected-(U1-PC20-Pad131)") (class "Default")
      (node (ref "U1") (pin "131") (pinfunction "PC20_131") (pintype "passive"))
    )
    (net (code "127") (name "unconnected-(U1-PC27-Pad138)") (class "Default")
      (node (ref "U1") (pin "138") (pinfunction "PC27_138") (pintype "passive"))
    )
    (net (code "128") (name "unconnected-(U1-SHDN-Pad50)") (class "Default")
      (node (ref "U1") (pin "50") (pinfunction "SHDN_50") (pintype "output"))
    )
  )
)
